# 4-20mA.net
KiCad netlist of a schematic drawn in EAGLE
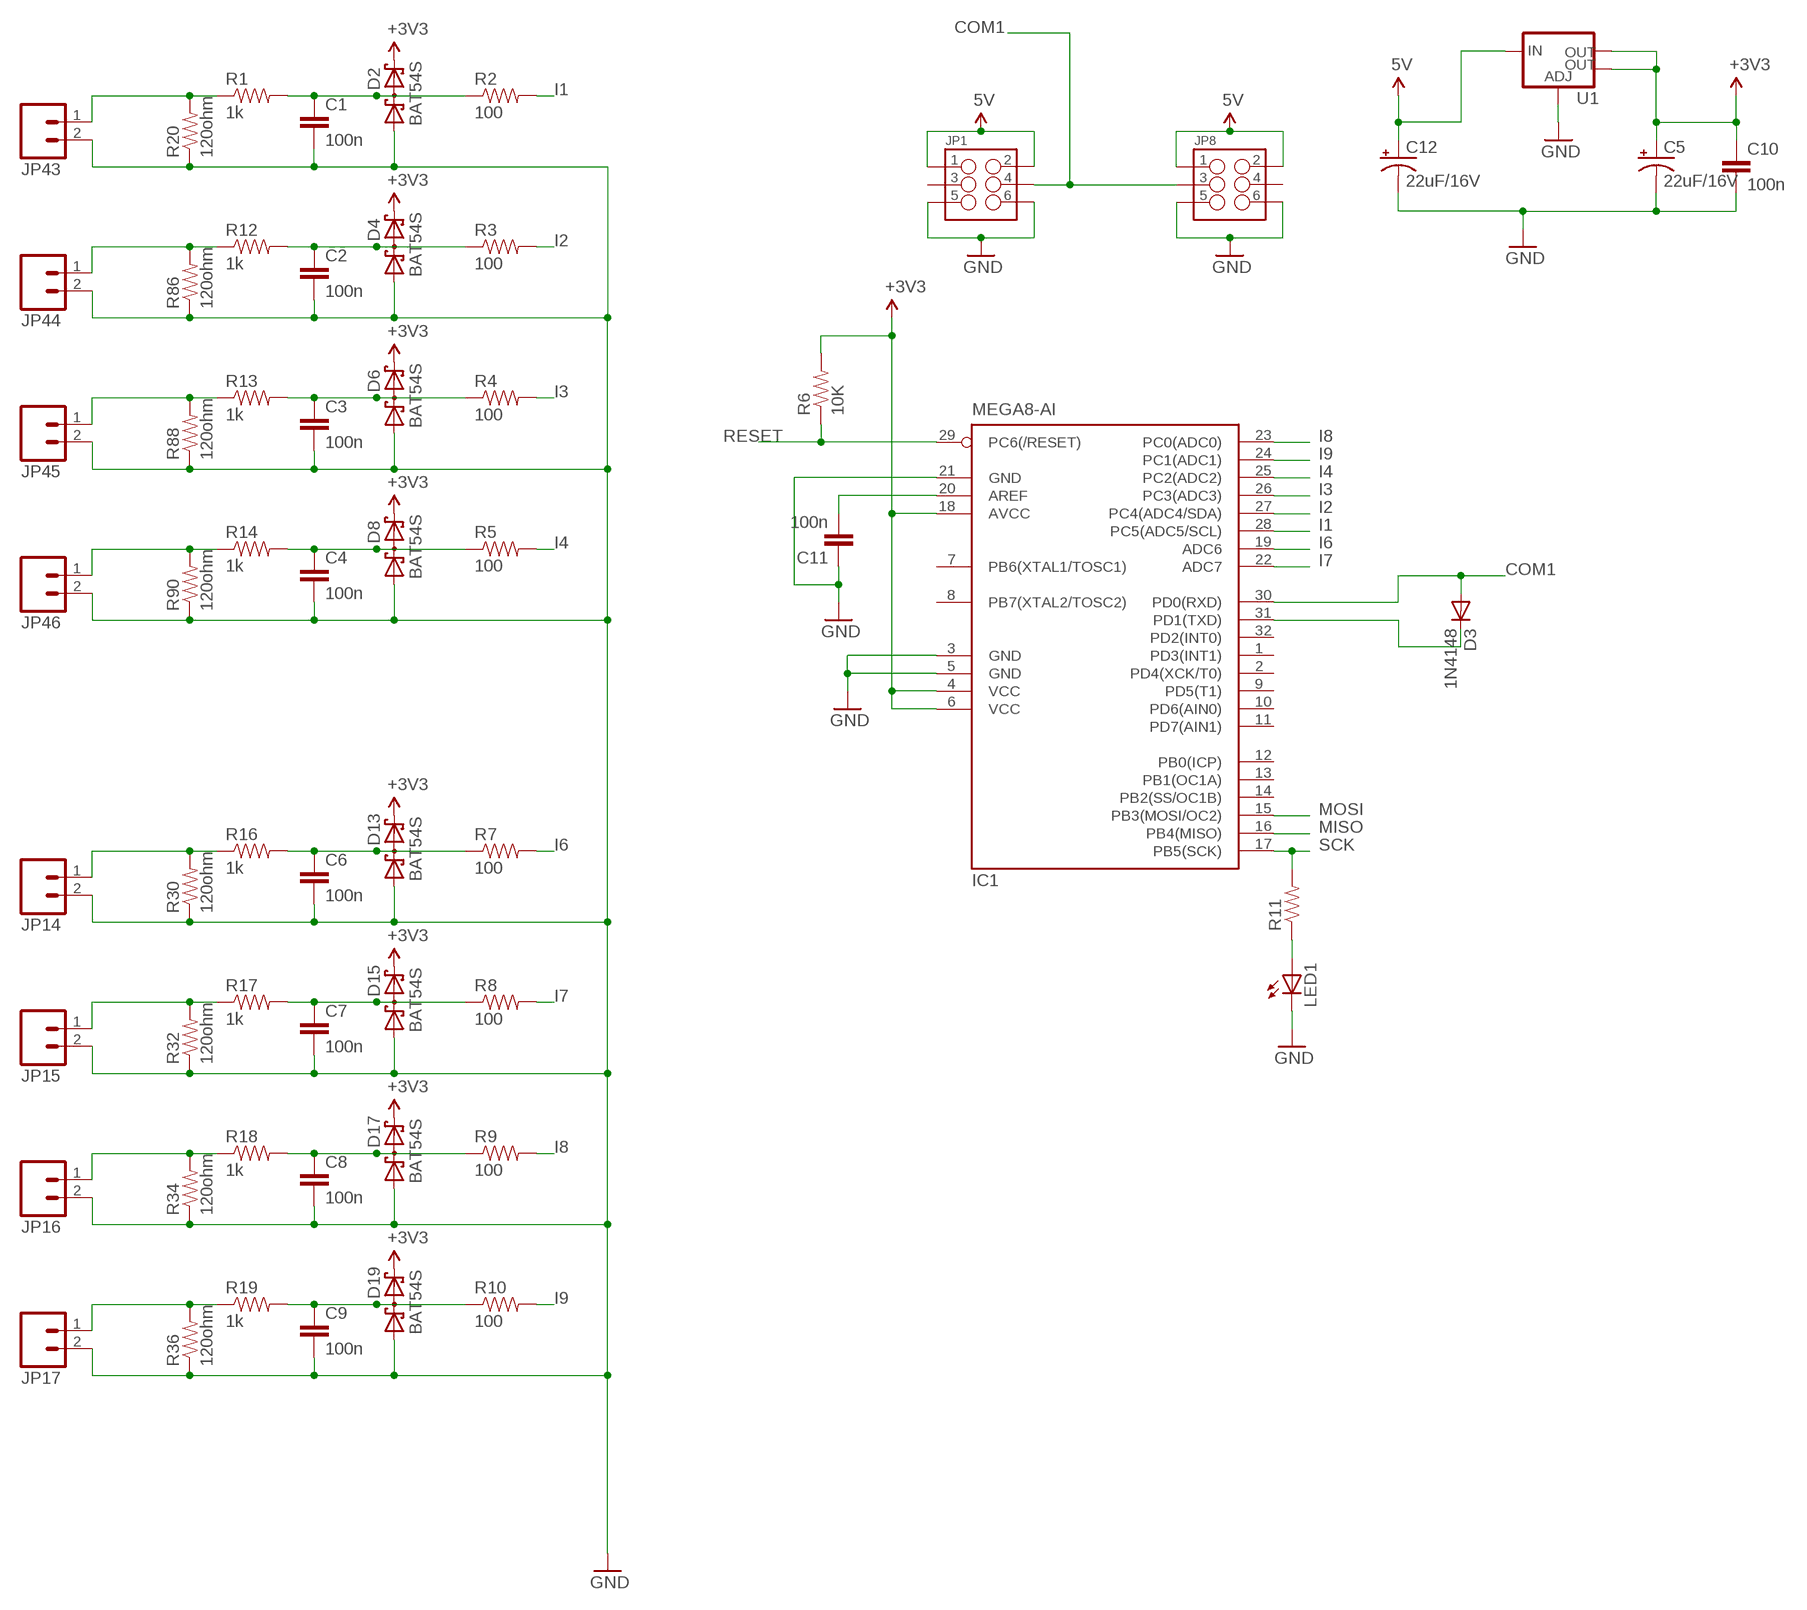
[diagram p0: schematic, sheet 1]

(export (version "E")
  (design (tool "Eeschema 10.0.6"))
  (components
    (comp (ref "C1")
      (value "100n")
      (footprint "eagle-import:0805")
      (libsource (lib "eagle-import") (part "CAP0805"))
    )
    (comp (ref "C2")
      (value "100n")
      (footprint "eagle-import:0805")
      (libsource (lib "eagle-import") (part "CAP0805"))
    )
    (comp (ref "C3")
      (value "100n")
      (footprint "eagle-import:0805")
      (libsource (lib "eagle-import") (part "CAP0805"))
    )
    (comp (ref "C4")
      (value "100n")
      (footprint "eagle-import:0805")
      (libsource (lib "eagle-import") (part "CAP0805"))
    )
    (comp (ref "C5")
      (value "22uF/16V")
      (footprint "eagle-import:EIA3216")
      (libsource (lib "eagle-import") (part "CAP_POL1206"))
    )
    (comp (ref "C6")
      (value "100n")
      (footprint "eagle-import:0805")
      (libsource (lib "eagle-import") (part "CAP0805"))
    )
    (comp (ref "C7")
      (value "100n")
      (footprint "eagle-import:0805")
      (libsource (lib "eagle-import") (part "CAP0805"))
    )
    (comp (ref "C8")
      (value "100n")
      (footprint "eagle-import:0805")
      (libsource (lib "eagle-import") (part "CAP0805"))
    )
    (comp (ref "C9")
      (value "100n")
      (footprint "eagle-import:0805")
      (libsource (lib "eagle-import") (part "CAP0805"))
    )
    (comp (ref "C10")
      (value "100n")
      (footprint "eagle-import:0805")
      (libsource (lib "eagle-import") (part "CAP0805"))
    )
    (comp (ref "C11")
      (value "100n")
      (footprint "eagle-import:0805")
      (libsource (lib "eagle-import") (part "CAP0805"))
    )
    (comp (ref "C12")
      (value "22uF/16V")
      (footprint "eagle-import:EIA3216")
      (libsource (lib "eagle-import") (part "CAP_POL1206"))
    )
    (comp (ref "D2")
      (value "BAT54S")
      (footprint "eagle-import:SOT23")
      (libsource (lib "eagle-import") (part "BAT54S"))
    )
    (comp (ref "D3")
      (value "1N4148")
      (footprint "eagle-import:MINIMELF")
      (libsource (lib "eagle-import") (part "DIODE-MINIMELF"))
    )
    (comp (ref "D4")
      (value "BAT54S")
      (footprint "eagle-import:SOT23")
      (libsource (lib "eagle-import") (part "BAT54S"))
    )
    (comp (ref "D6")
      (value "BAT54S")
      (footprint "eagle-import:SOT23")
      (libsource (lib "eagle-import") (part "BAT54S"))
    )
    (comp (ref "D8")
      (value "BAT54S")
      (footprint "eagle-import:SOT23")
      (libsource (lib "eagle-import") (part "BAT54S"))
    )
    (comp (ref "D13")
      (value "BAT54S")
      (footprint "eagle-import:SOT23")
      (libsource (lib "eagle-import") (part "BAT54S"))
    )
    (comp (ref "D15")
      (value "BAT54S")
      (footprint "eagle-import:SOT23")
      (libsource (lib "eagle-import") (part "BAT54S"))
    )
    (comp (ref "D17")
      (value "BAT54S")
      (footprint "eagle-import:SOT23")
      (libsource (lib "eagle-import") (part "BAT54S"))
    )
    (comp (ref "D19")
      (value "BAT54S")
      (footprint "eagle-import:SOT23")
      (libsource (lib "eagle-import") (part "BAT54S"))
    )
    (comp (ref "IC1")
      (value "MEGA8-AI")
      (footprint "eagle-import:TQFP32-08")
      (fields (field (name "MPN") "ATMEGA8-16AU"))
      (libsource (lib "eagle-import") (part "MEGA8-AI"))
    )
    (comp (ref "JP1")
      (value "M03X22X3_SILK_MALE_PTH")
      (footprint "eagle-import:2X3")
      (libsource (lib "eagle-import") (part "M03X22X3_SILK_MALE_PTH"))
    )
    (comp (ref "JP8")
      (value "M03X22X3_SILK_MALE_PTH")
      (footprint "eagle-import:2X3")
      (libsource (lib "eagle-import") (part "M03X22X3_SILK_MALE_PTH"))
    )
    (comp (ref "JP14")
      (value "M025MM")
      (footprint "eagle-import:SCREWTERMINAL-5MM-2")
      (libsource (lib "eagle-import") (part "M025MM"))
    )
    (comp (ref "JP15")
      (value "M025MM")
      (footprint "eagle-import:SCREWTERMINAL-5MM-2")
      (libsource (lib "eagle-import") (part "M025MM"))
    )
    (comp (ref "JP16")
      (value "M025MM")
      (footprint "eagle-import:SCREWTERMINAL-5MM-2")
      (libsource (lib "eagle-import") (part "M025MM"))
    )
    (comp (ref "JP17")
      (value "M025MM")
      (footprint "eagle-import:SCREWTERMINAL-5MM-2")
      (libsource (lib "eagle-import") (part "M025MM"))
    )
    (comp (ref "JP43")
      (value "M025MM")
      (footprint "eagle-import:SCREWTERMINAL-5MM-2")
      (libsource (lib "eagle-import") (part "M025MM"))
    )
    (comp (ref "JP44")
      (value "M025MM")
      (footprint "eagle-import:SCREWTERMINAL-5MM-2")
      (libsource (lib "eagle-import") (part "M025MM"))
    )
    (comp (ref "JP45")
      (value "M025MM")
      (footprint "eagle-import:SCREWTERMINAL-5MM-2")
      (libsource (lib "eagle-import") (part "M025MM"))
    )
    (comp (ref "JP46")
      (value "M025MM")
      (footprint "eagle-import:SCREWTERMINAL-5MM-2")
      (libsource (lib "eagle-import") (part "M025MM"))
    )
    (comp (ref "LED1")
      (value "LEDCHIP-LED0805")
      (footprint "eagle-import:CHIP-LED0805")
      (libsource (lib "eagle-import") (part "LEDCHIP-LED0805"))
    )
    (comp (ref "R1")
      (value "1k")
      (footprint "eagle-import:0805")
      (libsource (lib "eagle-import") (part "RESISTOR0805-RES"))
    )
    (comp (ref "R2")
      (value "100")
      (footprint "eagle-import:0805")
      (libsource (lib "eagle-import") (part "RESISTOR0805-RES"))
    )
    (comp (ref "R3")
      (value "100")
      (footprint "eagle-import:0805")
      (libsource (lib "eagle-import") (part "RESISTOR0805-RES"))
    )
    (comp (ref "R4")
      (value "100")
      (footprint "eagle-import:0805")
      (libsource (lib "eagle-import") (part "RESISTOR0805-RES"))
    )
    (comp (ref "R5")
      (value "100")
      (footprint "eagle-import:0805")
      (libsource (lib "eagle-import") (part "RESISTOR0805-RES"))
    )
    (comp (ref "R6")
      (value "10K")
      (footprint "eagle-import:0805")
      (libsource (lib "eagle-import") (part "RESISTOR0805-RES"))
    )
    (comp (ref "R7")
      (value "100")
      (footprint "eagle-import:0805")
      (libsource (lib "eagle-import") (part "RESISTOR0805-RES"))
    )
    (comp (ref "R8")
      (value "100")
      (footprint "eagle-import:0805")
      (libsource (lib "eagle-import") (part "RESISTOR0805-RES"))
    )
    (comp (ref "R9")
      (value "100")
      (footprint "eagle-import:0805")
      (libsource (lib "eagle-import") (part "RESISTOR0805-RES"))
    )
    (comp (ref "R10")
      (value "100")
      (footprint "eagle-import:0805")
      (libsource (lib "eagle-import") (part "RESISTOR0805-RES"))
    )
    (comp (ref "R11")
      (value "RESISTOR0805-RES")
      (footprint "eagle-import:0805")
      (libsource (lib "eagle-import") (part "RESISTOR0805-RES"))
    )
    (comp (ref "R12")
      (value "1k")
      (footprint "eagle-import:0805")
      (libsource (lib "eagle-import") (part "RESISTOR0805-RES"))
    )
    (comp (ref "R13")
      (value "1k")
      (footprint "eagle-import:0805")
      (libsource (lib "eagle-import") (part "RESISTOR0805-RES"))
    )
    (comp (ref "R14")
      (value "1k")
      (footprint "eagle-import:0805")
      (libsource (lib "eagle-import") (part "RESISTOR0805-RES"))
    )
    (comp (ref "R16")
      (value "1k")
      (footprint "eagle-import:0805")
      (libsource (lib "eagle-import") (part "RESISTOR0805-RES"))
    )
    (comp (ref "R17")
      (value "1k")
      (footprint "eagle-import:0805")
      (libsource (lib "eagle-import") (part "RESISTOR0805-RES"))
    )
    (comp (ref "R18")
      (value "1k")
      (footprint "eagle-import:0805")
      (libsource (lib "eagle-import") (part "RESISTOR0805-RES"))
    )
    (comp (ref "R19")
      (value "1k")
      (footprint "eagle-import:0805")
      (libsource (lib "eagle-import") (part "RESISTOR0805-RES"))
    )
    (comp (ref "R20")
      (value "120ohm")
      (footprint "eagle-import:R2010")
      (libsource (lib "eagle-import") (part "RESISTOR2010"))
    )
    (comp (ref "R30")
      (value "120ohm")
      (footprint "eagle-import:R2010")
      (libsource (lib "eagle-import") (part "RESISTOR2010"))
    )
    (comp (ref "R32")
      (value "120ohm")
      (footprint "eagle-import:R2010")
      (libsource (lib "eagle-import") (part "RESISTOR2010"))
    )
    (comp (ref "R34")
      (value "120ohm")
      (footprint "eagle-import:R2010")
      (libsource (lib "eagle-import") (part "RESISTOR2010"))
    )
    (comp (ref "R36")
      (value "120ohm")
      (footprint "eagle-import:R2010")
      (libsource (lib "eagle-import") (part "RESISTOR2010"))
    )
    (comp (ref "R86")
      (value "120ohm")
      (footprint "eagle-import:R2010")
      (libsource (lib "eagle-import") (part "RESISTOR2010"))
    )
    (comp (ref "R88")
      (value "120ohm")
      (footprint "eagle-import:R2010")
      (libsource (lib "eagle-import") (part "RESISTOR2010"))
    )
    (comp (ref "R90")
      (value "120ohm")
      (footprint "eagle-import:R2010")
      (libsource (lib "eagle-import") (part "RESISTOR2010"))
    )
    (comp (ref "U1")
      (value "V_REG_LM1117SOT223")
      (footprint "eagle-import:SOT223")
      (libsource (lib "eagle-import") (part "V_REG_LM1117SOT223"))
    )
  )
  (nets
    (net (code "1") (name "+3V3") (class "Default")
      (node (ref "C10") (pin "1") (pinfunction "1_1") (pintype "passive"))
      (node (ref "C5") (pin "A") (pinfunction "+_A") (pintype "passive"))
      (node (ref "D13") (pin "2") (pinfunction "C2_2") (pintype "passive"))
      (node (ref "D15") (pin "2") (pinfunction "C2_2") (pintype "passive"))
      (node (ref "D17") (pin "2") (pinfunction "C2_2") (pintype "passive"))
      (node (ref "D19") (pin "2") (pinfunction "C2_2") (pintype "passive"))
      (node (ref "D2") (pin "2") (pinfunction "C2_2") (pintype "passive"))
      (node (ref "D4") (pin "2") (pinfunction "C2_2") (pintype "passive"))
      (node (ref "D6") (pin "2") (pinfunction "C2_2") (pintype "passive"))
      (node (ref "D8") (pin "2") (pinfunction "C2_2") (pintype "passive"))
      (node (ref "IC1") (pin "18") (pinfunction "AVCC_18") (pintype "power_in"))
      (node (ref "IC1") (pin "4") (pinfunction "VCC_4") (pintype "power_in"))
      (node (ref "IC1") (pin "6") (pinfunction "VCC_6") (pintype "power_in"))
      (node (ref "R6") (pin "2") (pinfunction "2_2") (pintype "passive"))
      (node (ref "U1") (pin "2") (pinfunction "OUT_2") (pintype "output"))
      (node (ref "U1") (pin "4") (pinfunction "OUT_4") (pintype "output"))
    )
    (net (code "2") (name "/COM1") (class "Default")
      (node (ref "D3") (pin "A") (pinfunction "A_A") (pintype "passive"))
      (node (ref "IC1") (pin "30") (pinfunction "PD0(RXD)_30") (pintype "bidirectional"))
      (node (ref "JP1") (pin "4") (pinfunction "4_4") (pintype "bidirectional"))
      (node (ref "JP8") (pin "3") (pinfunction "3_3") (pintype "bidirectional"))
    )
    (net (code "3") (name "/I1") (class "Default")
      (node (ref "IC1") (pin "28") (pinfunction "PC5(ADC5/SCL)_28") (pintype "bidirectional"))
      (node (ref "R2") (pin "2") (pinfunction "2_2") (pintype "passive"))
    )
    (net (code "4") (name "/I2") (class "Default")
      (node (ref "IC1") (pin "27") (pinfunction "PC4(ADC4/SDA)_27") (pintype "bidirectional"))
      (node (ref "R3") (pin "2") (pinfunction "2_2") (pintype "passive"))
    )
    (net (code "5") (name "/I3") (class "Default")
      (node (ref "IC1") (pin "26") (pinfunction "PC3(ADC3)_26") (pintype "bidirectional"))
      (node (ref "R4") (pin "2") (pinfunction "2_2") (pintype "passive"))
    )
    (net (code "6") (name "/I4") (class "Default")
      (node (ref "IC1") (pin "25") (pinfunction "PC2(ADC2)_25") (pintype "bidirectional"))
      (node (ref "R5") (pin "2") (pinfunction "2_2") (pintype "passive"))
    )
    (net (code "7") (name "/I6") (class "Default")
      (node (ref "IC1") (pin "19") (pinfunction "ADC6_19") (pintype "bidirectional"))
      (node (ref "R7") (pin "2") (pinfunction "2_2") (pintype "passive"))
    )
    (net (code "8") (name "/I7") (class "Default")
      (node (ref "IC1") (pin "22") (pinfunction "ADC7_22") (pintype "bidirectional"))
      (node (ref "R8") (pin "2") (pinfunction "2_2") (pintype "passive"))
    )
    (net (code "9") (name "/I8") (class "Default")
      (node (ref "IC1") (pin "23") (pinfunction "PC0(ADC0)_23") (pintype "bidirectional"))
      (node (ref "R9") (pin "2") (pinfunction "2_2") (pintype "passive"))
    )
    (net (code "10") (name "/I9") (class "Default")
      (node (ref "IC1") (pin "24") (pinfunction "PC1(ADC1)_24") (pintype "bidirectional"))
      (node (ref "R10") (pin "2") (pinfunction "2_2") (pintype "passive"))
    )
    (net (code "11") (name "/MISO") (class "Default")
      (node (ref "IC1") (pin "16") (pinfunction "PB4(MISO)_16") (pintype "bidirectional"))
    )
    (net (code "12") (name "/MOSI") (class "Default")
      (node (ref "IC1") (pin "15") (pinfunction "PB3(MOSI/OC2)_15") (pintype "bidirectional"))
    )
    (net (code "13") (name "/RESET") (class "Default")
      (node (ref "IC1") (pin "29") (pinfunction "PC6(/RESET)_29") (pintype "bidirectional"))
      (node (ref "R6") (pin "1") (pinfunction "1_1") (pintype "passive"))
    )
    (net (code "14") (name "/SCK") (class "Default")
      (node (ref "IC1") (pin "17") (pinfunction "PB5(SCK)_17") (pintype "bidirectional"))
      (node (ref "R11") (pin "2") (pinfunction "2_2") (pintype "passive"))
    )
    (net (code "15") (name "5V") (class "Default")
      (node (ref "C12") (pin "A") (pinfunction "+_A") (pintype "passive"))
      (node (ref "JP1") (pin "1") (pinfunction "1_1") (pintype "bidirectional"))
      (node (ref "JP1") (pin "2") (pinfunction "2_2") (pintype "bidirectional"))
      (node (ref "JP8") (pin "1") (pinfunction "1_1") (pintype "bidirectional"))
      (node (ref "JP8") (pin "2") (pinfunction "2_2") (pintype "bidirectional"))
      (node (ref "U1") (pin "3") (pinfunction "IN_3") (pintype "input"))
    )
    (net (code "16") (name "GND") (class "Default")
      (node (ref "C1") (pin "2") (pinfunction "2_2") (pintype "passive"))
      (node (ref "C10") (pin "2") (pinfunction "2_2") (pintype "passive"))
      (node (ref "C11") (pin "1") (pinfunction "1_1") (pintype "passive"))
      (node (ref "C12") (pin "C") (pinfunction "-_C") (pintype "passive"))
      (node (ref "C2") (pin "2") (pinfunction "2_2") (pintype "passive"))
      (node (ref "C3") (pin "2") (pinfunction "2_2") (pintype "passive"))
      (node (ref "C4") (pin "2") (pinfunction "2_2") (pintype "passive"))
      (node (ref "C5") (pin "C") (pinfunction "-_C") (pintype "passive"))
      (node (ref "C6") (pin "2") (pinfunction "2_2") (pintype "passive"))
      (node (ref "C7") (pin "2") (pinfunction "2_2") (pintype "passive"))
      (node (ref "C8") (pin "2") (pinfunction "2_2") (pintype "passive"))
      (node (ref "C9") (pin "2") (pinfunction "2_2") (pintype "passive"))
      (node (ref "D13") (pin "1") (pinfunction "A1_1") (pintype "passive"))
      (node (ref "D15") (pin "1") (pinfunction "A1_1") (pintype "passive"))
      (node (ref "D17") (pin "1") (pinfunction "A1_1") (pintype "passive"))
      (node (ref "D19") (pin "1") (pinfunction "A1_1") (pintype "passive"))
      (node (ref "D2") (pin "1") (pinfunction "A1_1") (pintype "passive"))
      (node (ref "D4") (pin "1") (pinfunction "A1_1") (pintype "passive"))
      (node (ref "D6") (pin "1") (pinfunction "A1_1") (pintype "passive"))
      (node (ref "D8") (pin "1") (pinfunction "A1_1") (pintype "passive"))
      (node (ref "IC1") (pin "21") (pinfunction "GND_21") (pintype "power_in"))
      (node (ref "IC1") (pin "3") (pinfunction "GND_3") (pintype "power_in"))
      (node (ref "IC1") (pin "5") (pinfunction "GND_5") (pintype "power_in"))
      (node (ref "JP1") (pin "5") (pinfunction "5_5") (pintype "bidirectional"))
      (node (ref "JP1") (pin "6") (pinfunction "6_6") (pintype "bidirectional"))
      (node (ref "JP14") (pin "2") (pinfunction "2_2") (pintype "passive"))
      (node (ref "JP15") (pin "2") (pinfunction "2_2") (pintype "passive"))
      (node (ref "JP16") (pin "2") (pinfunction "2_2") (pintype "passive"))
      (node (ref "JP17") (pin "2") (pinfunction "2_2") (pintype "passive"))
      (node (ref "JP43") (pin "2") (pinfunction "2_2") (pintype "passive"))
      (node (ref "JP44") (pin "2") (pinfunction "2_2") (pintype "passive"))
      (node (ref "JP45") (pin "2") (pinfunction "2_2") (pintype "passive"))
      (node (ref "JP46") (pin "2") (pinfunction "2_2") (pintype "passive"))
      (node (ref "JP8") (pin "5") (pinfunction "5_5") (pintype "bidirectional"))
      (node (ref "JP8") (pin "6") (pinfunction "6_6") (pintype "bidirectional"))
      (node (ref "LED1") (pin "C") (pinfunction "C_C") (pintype "passive"))
      (node (ref "R20") (pin "1") (pinfunction "1_1") (pintype "passive"))
      (node (ref "R30") (pin "1") (pinfunction "1_1") (pintype "passive"))
      (node (ref "R32") (pin "1") (pinfunction "1_1") (pintype "passive"))
      (node (ref "R34") (pin "1") (pinfunction "1_1") (pintype "passive"))
      (node (ref "R36") (pin "1") (pinfunction "1_1") (pintype "passive"))
      (node (ref "R86") (pin "1") (pinfunction "1_1") (pintype "passive"))
      (node (ref "R88") (pin "1") (pinfunction "1_1") (pintype "passive"))
      (node (ref "R90") (pin "1") (pinfunction "1_1") (pintype "passive"))
      (node (ref "U1") (pin "1") (pinfunction "ADJ_1") (pintype "input"))
    )
    (net (code "17") (name "Net-(D2-C1A2)") (class "Default")
      (node (ref "C1") (pin "1") (pinfunction "1_1") (pintype "passive"))
      (node (ref "D2") (pin "3") (pinfunction "C1A2_3") (pintype "passive"))
      (node (ref "R1") (pin "2") (pinfunction "2_2") (pintype "passive"))
      (node (ref "R2") (pin "1") (pinfunction "1_1") (pintype "passive"))
    )
    (net (code "18") (name "Net-(D4-C1A2)") (class "Default")
      (node (ref "C2") (pin "1") (pinfunction "1_1") (pintype "passive"))
      (node (ref "D4") (pin "3") (pinfunction "C1A2_3") (pintype "passive"))
      (node (ref "R12") (pin "2") (pinfunction "2_2") (pintype "passive"))
      (node (ref "R3") (pin "1") (pinfunction "1_1") (pintype "passive"))
    )
    (net (code "19") (name "Net-(D6-C1A2)") (class "Default")
      (node (ref "C3") (pin "1") (pinfunction "1_1") (pintype "passive"))
      (node (ref "D6") (pin "3") (pinfunction "C1A2_3") (pintype "passive"))
      (node (ref "R13") (pin "2") (pinfunction "2_2") (pintype "passive"))
      (node (ref "R4") (pin "1") (pinfunction "1_1") (pintype "passive"))
    )
    (net (code "20") (name "Net-(D8-C1A2)") (class "Default")
      (node (ref "C4") (pin "1") (pinfunction "1_1") (pintype "passive"))
      (node (ref "D8") (pin "3") (pinfunction "C1A2_3") (pintype "passive"))
      (node (ref "R14") (pin "2") (pinfunction "2_2") (pintype "passive"))
      (node (ref "R5") (pin "1") (pinfunction "1_1") (pintype "passive"))
    )
    (net (code "21") (name "Net-(D13-C1A2)") (class "Default")
      (node (ref "C6") (pin "1") (pinfunction "1_1") (pintype "passive"))
      (node (ref "D13") (pin "3") (pinfunction "C1A2_3") (pintype "passive"))
      (node (ref "R16") (pin "2") (pinfunction "2_2") (pintype "passive"))
      (node (ref "R7") (pin "1") (pinfunction "1_1") (pintype "passive"))
    )
    (net (code "22") (name "Net-(D15-C1A2)") (class "Default")
      (node (ref "C7") (pin "1") (pinfunction "1_1") (pintype "passive"))
      (node (ref "D15") (pin "3") (pinfunction "C1A2_3") (pintype "passive"))
      (node (ref "R17") (pin "2") (pinfunction "2_2") (pintype "passive"))
      (node (ref "R8") (pin "1") (pinfunction "1_1") (pintype "passive"))
    )
    (net (code "23") (name "Net-(D17-C1A2)") (class "Default")
      (node (ref "C8") (pin "1") (pinfunction "1_1") (pintype "passive"))
      (node (ref "D17") (pin "3") (pinfunction "C1A2_3") (pintype "passive"))
      (node (ref "R18") (pin "2") (pinfunction "2_2") (pintype "passive"))
      (node (ref "R9") (pin "1") (pinfunction "1_1") (pintype "passive"))
    )
    (net (code "24") (name "Net-(D19-C1A2)") (class "Default")
      (node (ref "C9") (pin "1") (pinfunction "1_1") (pintype "passive"))
      (node (ref "D19") (pin "3") (pinfunction "C1A2_3") (pintype "passive"))
      (node (ref "R10") (pin "1") (pinfunction "1_1") (pintype "passive"))
      (node (ref "R19") (pin "2") (pinfunction "2_2") (pintype "passive"))
    )
    (net (code "25") (name "Net-(IC1-AREF)") (class "Default")
      (node (ref "C11") (pin "2") (pinfunction "2_2") (pintype "passive"))
      (node (ref "IC1") (pin "20") (pinfunction "AREF_20") (pintype "passive"))
    )
    (net (code "26") (name "Net-(IC1-PD1(TXD))") (class "Default")
      (node (ref "D3") (pin "C") (pinfunction "C_C") (pintype "passive"))
      (node (ref "IC1") (pin "31") (pinfunction "PD1(TXD)_31") (pintype "bidirectional"))
    )
    (net (code "27") (name "Net-(JP14-Pad1)") (class "Default")
      (node (ref "JP14") (pin "1") (pinfunction "1_1") (pintype "passive"))
      (node (ref "R16") (pin "1") (pinfunction "1_1") (pintype "passive"))
      (node (ref "R30") (pin "2") (pinfunction "2_2") (pintype "passive"))
    )
    (net (code "28") (name "Net-(JP15-Pad1)") (class "Default")
      (node (ref "JP15") (pin "1") (pinfunction "1_1") (pintype "passive"))
      (node (ref "R17") (pin "1") (pinfunction "1_1") (pintype "passive"))
      (node (ref "R32") (pin "2") (pinfunction "2_2") (pintype "passive"))
    )
    (net (code "29") (name "Net-(JP16-Pad1)") (class "Default")
      (node (ref "JP16") (pin "1") (pinfunction "1_1") (pintype "passive"))
      (node (ref "R18") (pin "1") (pinfunction "1_1") (pintype "passive"))
      (node (ref "R34") (pin "2") (pinfunction "2_2") (pintype "passive"))
    )
    (net (code "30") (name "Net-(JP17-Pad1)") (class "Default")
      (node (ref "JP17") (pin "1") (pinfunction "1_1") (pintype "passive"))
      (node (ref "R19") (pin "1") (pinfunction "1_1") (pintype "passive"))
      (node (ref "R36") (pin "2") (pinfunction "2_2") (pintype "passive"))
    )
    (net (code "31") (name "Net-(JP43-Pad1)") (class "Default")
      (node (ref "JP43") (pin "1") (pinfunction "1_1") (pintype "passive"))
      (node (ref "R1") (pin "1") (pinfunction "1_1") (pintype "passive"))
      (node (ref "R20") (pin "2") (pinfunction "2_2") (pintype "passive"))
    )
    (net (code "32") (name "Net-(JP44-Pad1)") (class "Default")
      (node (ref "JP44") (pin "1") (pinfunction "1_1") (pintype "passive"))
      (node (ref "R12") (pin "1") (pinfunction "1_1") (pintype "passive"))
      (node (ref "R86") (pin "2") (pinfunction "2_2") (pintype "passive"))
    )
    (net (code "33") (name "Net-(JP45-Pad1)") (class "Default")
      (node (ref "JP45") (pin "1") (pinfunction "1_1") (pintype "passive"))
      (node (ref "R13") (pin "1") (pinfunction "1_1") (pintype "passive"))
      (node (ref "R88") (pin "2") (pinfunction "2_2") (pintype "passive"))
    )
    (net (code "34") (name "Net-(JP46-Pad1)") (class "Default")
      (node (ref "JP46") (pin "1") (pinfunction "1_1") (pintype "passive"))
      (node (ref "R14") (pin "1") (pinfunction "1_1") (pintype "passive"))
      (node (ref "R90") (pin "2") (pinfunction "2_2") (pintype "passive"))
    )
    (net (code "35") (name "Net-(LED1-PadA)") (class "Default")
      (node (ref "LED1") (pin "A") (pinfunction "A_A") (pintype "passive"))
      (node (ref "R11") (pin "1") (pinfunction "1_1") (pintype "passive"))
    )
    (net (code "36") (name "unconnected-(IC1-PB0(ICP)-Pad12)") (class "Default")
      (node (ref "IC1") (pin "12") (pinfunction "PB0(ICP)_12") (pintype "bidirectional"))
    )
    (net (code "37") (name "unconnected-(IC1-PB1(OC1A)-Pad13)") (class "Default")
      (node (ref "IC1") (pin "13") (pinfunction "PB1(OC1A)_13") (pintype "bidirectional"))
    )
    (net (code "38") (name "unconnected-(IC1-PB2(SS{slash}OC1B)-Pad14)") (class "Default")
      (node (ref "IC1") (pin "14") (pinfunction "PB2(SS/OC1B)_14") (pintype "bidirectional"))
    )
    (net (code "39") (name "unconnected-(IC1-PB6(XTAL1{slash}TOSC1)-Pad7)") (class "Default")
      (node (ref "IC1") (pin "7") (pinfunction "PB6(XTAL1/TOSC1)_7") (pintype "bidirectional"))
    )
    (net (code "40") (name "unconnected-(IC1-PB7(XTAL2{slash}TOSC2)-Pad8)") (class "Default")
      (node (ref "IC1") (pin "8") (pinfunction "PB7(XTAL2/TOSC2)_8") (pintype "bidirectional"))
    )
    (net (code "41") (name "unconnected-(IC1-PD2(INT0)-Pad32)") (class "Default")
      (node (ref "IC1") (pin "32") (pinfunction "PD2(INT0)_32") (pintype "bidirectional"))
    )
    (net (code "42") (name "unconnected-(IC1-PD3(INT1)-Pad1)") (class "Default")
      (node (ref "IC1") (pin "1") (pinfunction "PD3(INT1)_1") (pintype "bidirectional"))
    )
    (net (code "43") (name "unconnected-(IC1-PD4(XCK{slash}T0)-Pad2)") (class "Default")
      (node (ref "IC1") (pin "2") (pinfunction "PD4(XCK/T0)_2") (pintype "bidirectional"))
    )
    (net (code "44") (name "unconnected-(IC1-PD5(T1)-Pad9)") (class "Default")
      (node (ref "IC1") (pin "9") (pinfunction "PD5(T1)_9") (pintype "bidirectional"))
    )
    (net (code "45") (name "unconnected-(IC1-PD6(AIN0)-Pad10)") (class "Default")
      (node (ref "IC1") (pin "10") (pinfunction "PD6(AIN0)_10") (pintype "bidirectional"))
    )
    (net (code "46") (name "unconnected-(IC1-PD7(AIN1)-Pad11)") (class "Default")
      (node (ref "IC1") (pin "11") (pinfunction "PD7(AIN1)_11") (pintype "bidirectional"))
    )
    (net (code "47") (name "unconnected-(JP1-Pad3)") (class "Default")
      (node (ref "JP1") (pin "3") (pinfunction "3_3") (pintype "bidirectional"))
    )
    (net (code "48") (name "unconnected-(JP8-Pad4)") (class "Default")
      (node (ref "JP8") (pin "4") (pinfunction "4_4") (pintype "bidirectional"))
    )
  )
)
